# TIDA-010933-DCDC-Power.net
KiCad netlist of a schematic drawn in Altium Designer
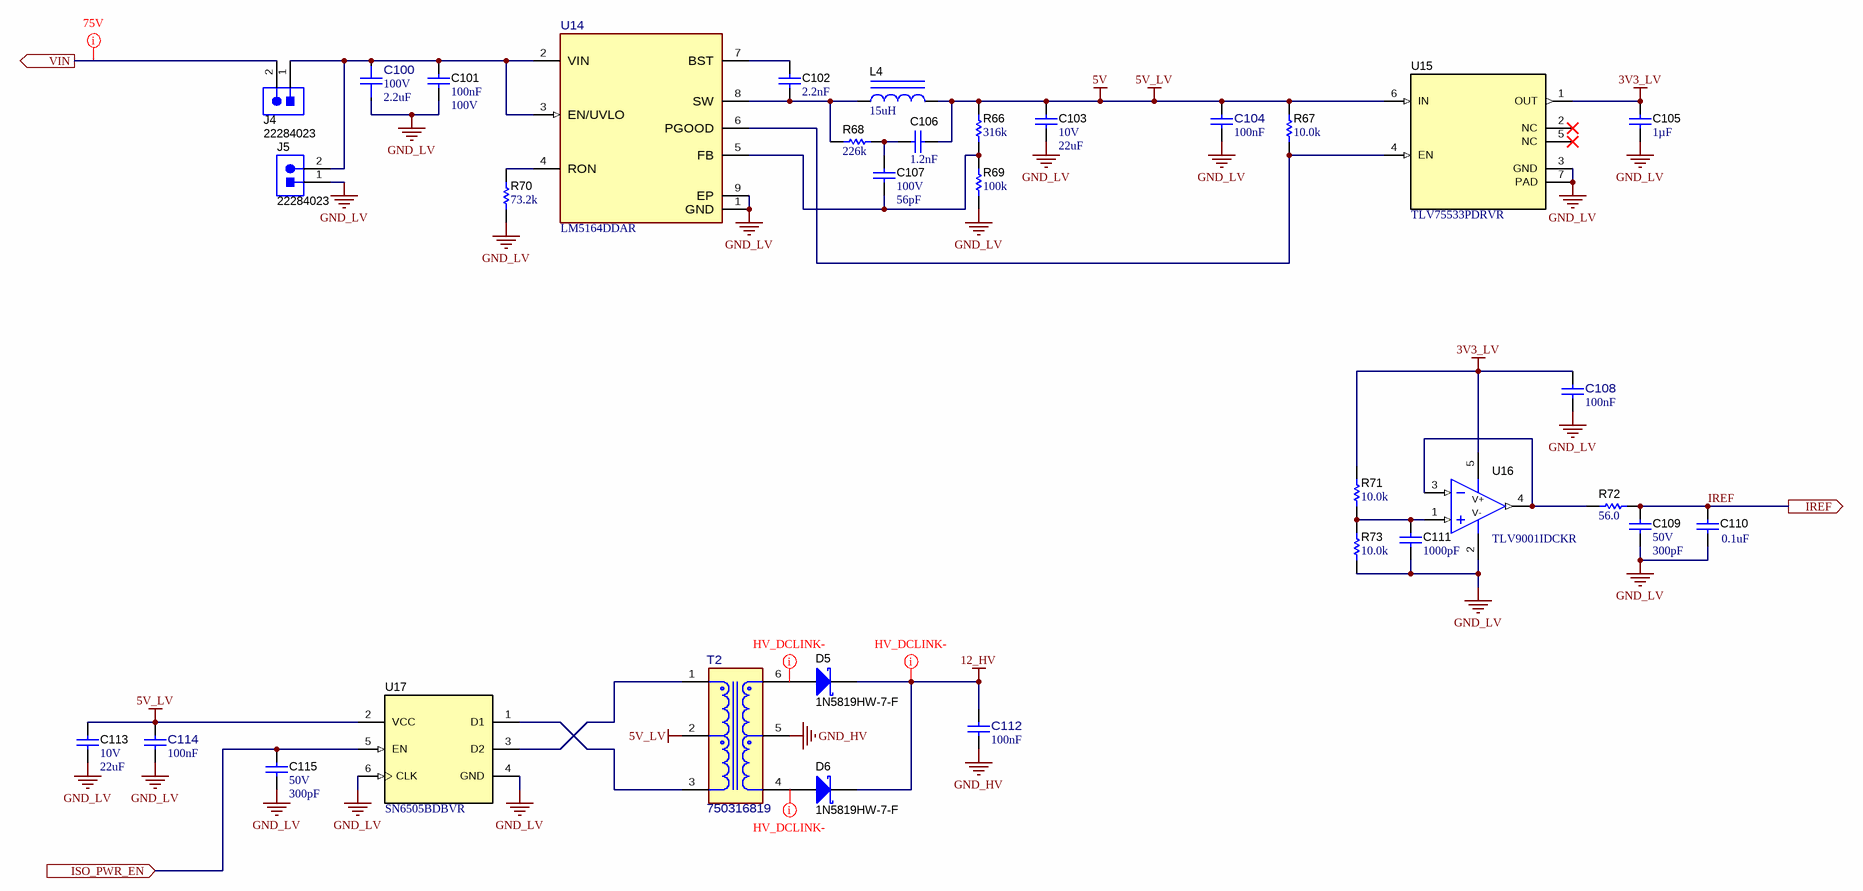
[diagram p0: TIDA-010933-DCDC-Power.SchDoc]

(export (version "E")
  (design (tool "Eeschema 10.0.6"))
  (components
    (comp (ref "C100")
      (value "C3225X7R2A225K230AB")
      (footprint "FP-C3225X7R2A225K230AB_1210-MFG")
      (description "CAP, CERM, 2.2 uF, 100 V, +/- 10%, X7R, 1210")
      (fields
        (field (name "VDC_V") "100V")
        (field (name "MANUFACTURER") "TDK")
        (field (name "VALUEDISPLAYED") "2.2uF")
      )
      (libsource (lib "Altium Vault - TI") (part "SYM-C3225X7R2A225K230AB"))
    )
    (comp (ref "C101")
      (value "GRM188R72A104KA35D")
      (footprint "0603")
      (description "CAP, CERM, 0.1 uF, 100 V, +/- 10%, X7R, 0603")
      (fields
        (field (name "MANUFACTURER") "MuRata")
        (field (name "CAP_F") "100nF")
        (field (name "VDC_V") "100V")
        (field (name "PUBLISHER") "Texas Instruments")
      )
      (libsource (lib "Altium Vault - TI") (part "Capacitor"))
    )
    (comp (ref "C102")
      (value "C0603C222K5RAC")
      (footprint "0603")
      (description "CAP, CERM, 2200 pF, 50 V, +/- 10%, X7R, 0603")
      (fields
        (field (name "MANUFACTURER") "Kemet")
        (field (name "CAP_F") "2.2nF")
        (field (name "PUBLISHER") "Texas Instruments")
      )
      (libsource (lib "Altium Vault - TI") (part "Capacitor"))
    )
    (comp (ref "C103")
      (value "GRM31CR71A226KE15L")
      (footprint "1206_180")
      (description "CAP, CERM, 22 uF, 10 V, +/- 10%, X7R, 1206")
      (fields
        (field (name "MANUFACTURER") "MuRata")
        (field (name "VDC_V") "10V")
        (field (name "VALUEDISPLAYED") "22uF")
        (field (name "PUBLISHER") "Texas Instruments")
      )
      (libsource (lib "Altium Vault - TI") (part "Capacitor"))
    )
    (comp (ref "C104")
      (value "CL10B104KB8NNNC")
      (footprint "FP-CL10B104KB8NNNC_0603-IPC_B")
      (description "CAP CER 0.1UF 50V X7R 0603")
      (fields (field (name "CAP_F") "100nF") (field (name "MANUFACTURER") "Samsung"))
      (libsource (lib "Altium Vault - TI") (part "SYM-CAPACITOR"))
    )
    (comp (ref "C105")
      (value "885012206026")
      (footprint "0603")
      (description "CAP, CERM, 1 uF, 10 V,+/- 10%, X7R, 0603")
      (fields
        (field (name "MANUFACTURER") "Wurth Elektronik")
        (field (name "CAP_F") "1µF")
        (field (name "PUBLISHER") "Texas Instruments")
      )
      (libsource (lib "Altium Vault - TI") (part "Capacitor"))
    )
    (comp (ref "C106")
      (value "GRM188R72A122KA01D")
      (footprint "0603")
      (description "CAP, CERM, 1200 pF, 100 V, +/- 10%, X7R, 0603")
      (fields
        (field (name "MANUFACTURER") "MuRata")
        (field (name "CAP_F") "1.2nF")
        (field (name "PUBLISHER") "Texas Instruments")
      )
      (libsource (lib "Altium Vault - TI") (part "Capacitor"))
    )
    (comp (ref "C107")
      (value "GRM1885C2A560JA01D")
      (footprint "0603")
      (description "CAP, CERM, 56 pF, 100 V, +/- 5%, C0G/NP0, 0603")
      (fields
        (field (name "MANUFACTURER") "MuRata")
        (field (name "VDC_V") "100V")
        (field (name "VALUEDISPLAYED") "56pF")
        (field (name "PUBLISHER") "Texas Instruments")
      )
      (libsource (lib "Altium Vault - TI") (part "Capacitor"))
    )
    (comp (ref "C108")
      (value "CL10B104KB8NNNC")
      (footprint "FP-CL10B104KB8NNNC_0603-IPC_B")
      (description "CAP CER 0.1UF 50V X7R 0603")
      (fields (field (name "CAP_F") "100nF") (field (name "MANUFACTURER") "Samsung"))
      (libsource (lib "Altium Vault - TI") (part "SYM-CAPACITOR"))
    )
    (comp (ref "C109")
      (value "GRM1885C1H301JA01D")
      (footprint "0603")
      (description "CAP, CERM, 300 pF, 50 V, +/- 5%, C0G/NP0, 0603")
      (fields
        (field (name "MANUFACTURER") "MuRata")
        (field (name "VDC_V") "50V")
        (field (name "VALUEDISPLAYED") "300pF")
        (field (name "PUBLISHER") "Texas Instruments")
      )
      (libsource (lib "Altium Vault - TI") (part "Capacitor"))
    )
    (comp (ref "C110")
      (value "GRM155R71E104KE14D")
      (footprint "0402")
      (description "CAP, CERM, 0.1 uF, 25 V, +/- 10%, X7R, 0402")
      (fields
        (field (name "MANUFACTURER") "MuRata")
        (field (name "VALUEDISPLAYED") "0.1uF")
        (field (name "PUBLISHER") "Texas Instruments")
      )
      (libsource (lib "Altium Vault - TI") (part "Capacitor"))
    )
    (comp (ref "C111")
      (value "CC0603JRNPO8BN102")
      (footprint "0603")
      (description "CAP, CERM, 1000 pF, 25 V,+/- 5%, C0G/NP0, 0603")
      (fields (field (name "VALUEDISPLAYED") "1000pF") (field (name "MANUFACTURER") "Yageo"))
      (libsource (lib "Altium Vault - TI") (part "Capacitor"))
    )
    (comp (ref "C112")
      (value "CL10B104KB8NNNC")
      (footprint "FP-CL10B104KB8NNNC_0603-IPC_B")
      (description "CAP CER 0.1UF 50V X7R 0603")
      (fields (field (name "CAP_F") "100nF") (field (name "MANUFACTURER") "Samsung"))
      (libsource (lib "Altium Vault - TI") (part "SYM-CAPACITOR"))
    )
    (comp (ref "C113")
      (value "GRM31CR71A226KE15L")
      (footprint "1206_180")
      (description "CAP, CERM, 22 uF, 10 V, +/- 10%, X7R, 1206")
      (fields
        (field (name "MANUFACTURER") "MuRata")
        (field (name "VDC_V") "10V")
        (field (name "VALUEDISPLAYED") "22uF")
        (field (name "PUBLISHER") "Texas Instruments")
      )
      (libsource (lib "Altium Vault - TI") (part "Capacitor"))
    )
    (comp (ref "C114")
      (value "CL10B104KB8NNNC")
      (footprint "FP-CL10B104KB8NNNC_0603-IPC_B")
      (description "CAP CER 0.1UF 50V X7R 0603")
      (fields (field (name "CAP_F") "100nF") (field (name "MANUFACTURER") "Samsung"))
      (libsource (lib "Altium Vault - TI") (part "SYM-CAPACITOR"))
    )
    (comp (ref "C115")
      (value "GRM1885C1H301JA01D")
      (footprint "0603")
      (description "CAP, CERM, 300 pF, 50 V, +/- 5%, C0G/NP0, 0603")
      (fields
        (field (name "MANUFACTURER") "MuRata")
        (field (name "VDC_V") "50V")
        (field (name "VALUEDISPLAYED") "300pF")
        (field (name "PUBLISHER") "Texas Instruments")
      )
      (libsource (lib "Altium Vault - TI") (part "Capacitor"))
    )
    (comp (ref "D5")
      (value "1N5819HW-7-F")
      (footprint "SOD-123")
      (description "Diode, Schottky, 40 V, 1 A, SOD-123")
      (fields (field (name "MANUFACTURER") "Diodes Inc."))
      (libsource (lib "Altium Vault - TI") (part "DIODE_SCHOTTKY"))
    )
    (comp (ref "D6")
      (value "1N5819HW-7-F")
      (footprint "SOD-123")
      (description "Diode, Schottky, 40 V, 1 A, SOD-123")
      (fields (field (name "MANUFACTURER") "Diodes Inc."))
      (libsource (lib "Altium Vault - TI") (part "DIODE_SCHOTTKY"))
    )
    (comp (ref "J4")
      (value "22284023")
      (footprint "Molex_0022284023")
      (description "Header, 2.54mm, 2x1, Tin, TH")
      (fields (field (name "MANUFACTURER") "Molex") (field (name "PUBLISHER") "Texas Instruments"))
      (libsource (lib "") (part "Header_2x1_1"))
    )
    (comp (ref "J5")
      (value "22284023")
      (footprint "Molex_0022284023")
      (description "Header, 2.54mm, 2x1, Tin, TH")
      (fields (field (name "MANUFACTURER") "Molex") (field (name "PUBLISHER") "Texas Instruments"))
      (libsource (lib "Altium Vault - TI") (part "Header_2x1"))
    )
    (comp (ref "L4")
      (value "SRP6540-150M")
      (footprint "SRP6540")
      (description "Inductor, Shielded, Ferrite, 15 uH, 2.9 A, 0.121 ohm, SMD")
      (fields
        (field (name "MANUFACTURER") "Bourns")
        (field (name "VALUEDISPLAYED") "15uH")
        (field (name "PUBLISHER") "Texas Instruments")
      )
      (libsource (lib "Altium Vault - TI") (part "Inductor_Iron"))
    )
    (comp (ref "R66")
      (value "RC0603FR-07316KL")
      (footprint "0603")
      (description "RES, 316 k, 1%, 0.1 W, 0603")
      (fields (field (name "MANUFACTURER") "Yageo") (field (name "VALUEDISPLAYED") "316k"))
      (libsource (lib "Altium Vault - TI") (part "Resistor"))
    )
    (comp (ref "R67")
      (value "RC0402FR-0710KL")
      (footprint "0402")
      (description "RES, 10.0 k, 1%, 0.063 W, 0402")
      (fields (field (name "MANUFACTURER") "Yageo America") (field (name "VALUEDISPLAYED") "10.0k"))
      (libsource (lib "Altium Vault - TI") (part "Resistor"))
    )
    (comp (ref "R68")
      (value "RC0603FR-07226KL")
      (footprint "0603")
      (description "RES, 226 k, 1%, 0.1 W, 0603")
      (fields (field (name "MANUFACTURER") "Yageo") (field (name "VALUEDISPLAYED") "226k"))
      (libsource (lib "Altium Vault - TI") (part "Resistor"))
    )
    (comp (ref "R69")
      (value "RC0603FR-07100KL")
      (footprint "0603")
      (description "RES, 100 k, 1%, 0.1 W, 0603")
      (fields (field (name "MANUFACTURER") "Yageo") (field (name "VALUEDISPLAYED") "100k"))
      (libsource (lib "Altium Vault - TI") (part "Resistor"))
    )
    (comp (ref "R70")
      (value "RC0603FR-0773K2L")
      (footprint "0603")
      (description "RES, 73.2 k, 1%, 0.1 W, 0603")
      (fields (field (name "MANUFACTURER") "Yageo") (field (name "VALUEDISPLAYED") "73.2k"))
      (libsource (lib "Altium Vault - TI") (part "Resistor"))
    )
    (comp (ref "R71")
      (value "RT0603BRD0710KL")
      (footprint "0603")
      (description "RES, 10.0 k, 0.1%, 0.1 W, 0603")
      (fields
        (field (name "MANUFACTURER") "Yageo America")
        (field (name "VALUEDISPLAYED") "10.0k")
        (field (name "PUBLISHER") "Texas Instruments")
      )
      (libsource (lib "Altium Vault - TI") (part "Resistor"))
    )
    (comp (ref "R72")
      (value "RC0603FR-0756RL")
      (footprint "0603")
      (description "RES, 56.0, 1%, 0.1 W, 0603")
      (fields (field (name "MANUFACTURER") "Yageo") (field (name "VALUEDISPLAYED") "56.0"))
      (libsource (lib "Altium Vault - TI") (part "Resistor"))
    )
    (comp (ref "R73")
      (value "RT0603BRD0710KL")
      (footprint "0603")
      (description "RES, 10.0 k, 0.1%, 0.1 W, 0603")
      (fields
        (field (name "MANUFACTURER") "Yageo America")
        (field (name "VALUEDISPLAYED") "10.0k")
        (field (name "PUBLISHER") "Texas Instruments")
      )
      (libsource (lib "Altium Vault - TI") (part "Resistor"))
    )
    (comp (ref "T2")
      (value "750316819")
      (footprint "FP-750316819_SMT_XFRMR_9MM25_8MM30-MFG")
      (fields
        (field (name "MOUSER PART NUMBER") "710-750316819")
        (field (name "DIGIKEY PART NUMBER") "732-750316819CT-ND")
        (field (name "MANUFACTURER") "Wurth Electronics")
      )
      (libsource (lib "Altium Vault - TI") (part "SYM-750316819"))
    )
    (comp (ref "U14")
      (value "LM5164DDAR")
      (footprint "DDA0008E-MFG")
      (fields
        (field (name "PARTNUMBER") "LM5164DDAR")
        (field (name "MOUSER PART NUMBER") "595-LM5164DDAR")
        (field (name "MANUFACTURER") "Texas Instruments")
        (field (name "DIGIKEY PART NUMBER") "296-LM5164DDARCT-ND")
      )
      (libsource (lib "Altium Vault - TI") (part "SYM-LM5164DDAR"))
    )
    (comp (ref "U15")
      (value "TLV75533PDRVR")
      (footprint "DRV0006A")
      (description "500mA LDO, DRV0006A (WSON-6)")
      (fields
        (field (name "PARTNUMBER") "TLV75533PDRVR")
        (field (name "MANUFACTURER") "Texas Instruments")
        (field (name "PUBLISHER") "Texas Instruments")
      )
      (libsource (lib "Altium Vault - TI") (part "TLV75533PDRV"))
    )
    (comp (ref "U16")
      (value "TLV9001IDCKR")
      (footprint "DCK0005A_N")
      (description "Low-Power, Rail-to-Rail In and Out, 1-MHz Operational Amplifier, DCK0005A (SOT-SC70-5)")
      (fields
        (field (name "ALTERNATE PARTNUMBER") "TLV9001IDCKT")
        (field (name "MANUFACTURER") "Texas Instruments")
        (field (name "PARTNUMBER") "TLV9001IDCKR")
      )
      (libsource (lib "Altium Vault - TI") (part "OPAMP_SINGLE_SOT321"))
    )
    (comp (ref "U17")
      (value "SN6505BDBVR")
      (footprint "DBV0006A_L")
      (description "Low-Noise 1 A, 420 kHz Transformer Driver, DBV0006A (SOT-23-6)")
      (fields
        (field (name "PARTNUMBER") "SN6505BDBVR")
        (field (name "MANUFACTURER") "Texas Instruments")
        (field (name "ALTERNATE PARTNUMBER") "SN6505BDBVT")
        (field (name "PUBLISHER") "Texas Instruments")
      )
      (libsource (lib "Altium Vault - TI") (part "SN6505"))
    )
  )
  (nets
    (net (code "1") (name "/IREF") (class "Default")
      (node (ref "C109") (pin "1") (pinfunction "1_1") (pintype "passive"))
      (node (ref "C110") (pin "1") (pinfunction "1_1") (pintype "passive"))
      (node (ref "R72") (pin "2") (pinfunction "2_2") (pintype "passive"))
    )
    (net (code "2") (name "/ISO_PWR_EN") (class "Default")
      (node (ref "C115") (pin "1") (pinfunction "1_1") (pintype "passive"))
      (node (ref "U17") (pin "5") (pinfunction "EN_5") (pintype "input"))
    )
    (net (code "3") (name "/VIN") (class "Default")
      (node (ref "J4") (pin "2") (pinfunction "2_2") (pintype "passive"))
    )
    (net (code "4") (name "3V3_LV") (class "Default")
      (node (ref "C105") (pin "1") (pinfunction "1_1") (pintype "passive"))
      (node (ref "C108") (pin "1") (pinfunction "1_1") (pintype "passive"))
      (node (ref "R71") (pin "1") (pinfunction "1_1") (pintype "passive"))
      (node (ref "U15") (pin "1") (pinfunction "OUT_1") (pintype "output"))
      (node (ref "U16") (pin "5") (pinfunction "V+_5") (pintype "power_in"))
    )
    (net (code "5") (name "5V") (class "Default")
      (node (ref "C103") (pin "1") (pinfunction "1_1") (pintype "passive"))
      (node (ref "C104") (pin "2") (pinfunction "2_2") (pintype "passive"))
      (node (ref "C106") (pin "1") (pinfunction "1_1") (pintype "passive"))
      (node (ref "C113") (pin "1") (pinfunction "1_1") (pintype "passive"))
      (node (ref "C114") (pin "1") (pinfunction "1_1") (pintype "passive"))
      (node (ref "L4") (pin "2") (pinfunction "2_2") (pintype "passive"))
      (node (ref "R66") (pin "2") (pinfunction "2_2") (pintype "passive"))
      (node (ref "R67") (pin "2") (pinfunction "2_2") (pintype "passive"))
      (node (ref "T2") (pin "2") (pinfunction "2_2") (pintype "passive"))
      (node (ref "U15") (pin "6") (pinfunction "IN_6") (pintype "input"))
      (node (ref "U17") (pin "2") (pinfunction "VCC_2") (pintype "power_in"))
    )
    (net (code "6") (name "12_HV") (class "Default")
      (node (ref "C112") (pin "1") (pinfunction "1_1") (pintype "passive"))
      (node (ref "D5") (pin "1") (pinfunction "K_1") (pintype "passive"))
      (node (ref "D6") (pin "1") (pinfunction "K_1") (pintype "passive"))
    )
    (net (code "7") (name "GND_HV") (class "Default")
      (node (ref "C112") (pin "2") (pinfunction "2_2") (pintype "passive"))
      (node (ref "T2") (pin "5") (pinfunction "5_5") (pintype "passive"))
    )
    (net (code "8") (name "GND_LV") (class "Default")
      (node (ref "C100") (pin "1") (pinfunction "1_1") (pintype "passive"))
      (node (ref "C101") (pin "2") (pinfunction "2_2") (pintype "passive"))
      (node (ref "C103") (pin "2") (pinfunction "2_2") (pintype "passive"))
      (node (ref "C104") (pin "1") (pinfunction "1_1") (pintype "passive"))
      (node (ref "C105") (pin "2") (pinfunction "2_2") (pintype "passive"))
      (node (ref "C108") (pin "2") (pinfunction "2_2") (pintype "passive"))
      (node (ref "C109") (pin "2") (pinfunction "2_2") (pintype "passive"))
      (node (ref "C110") (pin "2") (pinfunction "2_2") (pintype "passive"))
      (node (ref "C111") (pin "2") (pinfunction "2_2") (pintype "passive"))
      (node (ref "C113") (pin "2") (pinfunction "2_2") (pintype "passive"))
      (node (ref "C114") (pin "2") (pinfunction "2_2") (pintype "passive"))
      (node (ref "C115") (pin "2") (pinfunction "2_2") (pintype "passive"))
      (node (ref "J5") (pin "1") (pinfunction "1_1") (pintype "passive"))
      (node (ref "R69") (pin "1") (pinfunction "1_1") (pintype "passive"))
      (node (ref "R70") (pin "1") (pinfunction "1_1") (pintype "passive"))
      (node (ref "R73") (pin "2") (pinfunction "2_2") (pintype "passive"))
      (node (ref "U14") (pin "1") (pinfunction "GND_1") (pintype "power_in"))
      (node (ref "U14") (pin "9") (pinfunction "EP_9") (pintype "passive"))
      (node (ref "U15") (pin "3") (pinfunction "GND_3") (pintype "power_in"))
      (node (ref "U15") (pin "7") (pinfunction "PAD_7") (pintype "power_in"))
      (node (ref "U16") (pin "2") (pinfunction "V-_2") (pintype "power_in"))
      (node (ref "U17") (pin "4") (pinfunction "GND_4") (pintype "power_in"))
      (node (ref "U17") (pin "6") (pinfunction "CLK_6") (pintype "input"))
    )
    (net (code "9") (name "Net-(C106-Pad2)") (class "Default")
      (node (ref "C106") (pin "2") (pinfunction "2_2") (pintype "passive"))
      (node (ref "C107") (pin "1") (pinfunction "1_1") (pintype "passive"))
      (node (ref "R68") (pin "2") (pinfunction "2_2") (pintype "passive"))
    )
    (net (code "10") (name "Net-(D5-A)") (class "Default")
      (node (ref "D5") (pin "2") (pinfunction "A_2") (pintype "passive"))
      (node (ref "T2") (pin "6") (pinfunction "6_6") (pintype "passive"))
    )
    (net (code "11") (name "Net-(D6-A)") (class "Default")
      (node (ref "D6") (pin "2") (pinfunction "A_2") (pintype "passive"))
      (node (ref "T2") (pin "4") (pinfunction "4_4") (pintype "passive"))
    )
    (net (code "12") (name "Net-(U14-BST)") (class "Default")
      (node (ref "C102") (pin "1") (pinfunction "1_1") (pintype "passive"))
      (node (ref "U14") (pin "7") (pinfunction "BST_7") (pintype "passive"))
    )
    (net (code "13") (name "Net-(U14-EN{slash}UVLO)") (class "Default")
      (node (ref "C100") (pin "2") (pinfunction "2_2") (pintype "passive"))
      (node (ref "C101") (pin "1") (pinfunction "1_1") (pintype "passive"))
      (node (ref "J4") (pin "1") (pinfunction "1_1") (pintype "passive"))
      (node (ref "J5") (pin "2") (pinfunction "2_2") (pintype "passive"))
      (node (ref "U14") (pin "2") (pinfunction "VIN_2") (pintype "power_in"))
      (node (ref "U14") (pin "3") (pinfunction "EN/UVLO_3") (pintype "input"))
    )
    (net (code "14") (name "Net-(U14-FB)") (class "Default")
      (node (ref "C107") (pin "2") (pinfunction "2_2") (pintype "passive"))
      (node (ref "R66") (pin "1") (pinfunction "1_1") (pintype "passive"))
      (node (ref "R69") (pin "2") (pinfunction "2_2") (pintype "passive"))
      (node (ref "U14") (pin "5") (pinfunction "FB_5") (pintype "passive"))
    )
    (net (code "15") (name "Net-(U14-PGOOD)") (class "Default")
      (node (ref "R67") (pin "1") (pinfunction "1_1") (pintype "passive"))
      (node (ref "U14") (pin "6") (pinfunction "PGOOD_6") (pintype "open_collector"))
      (node (ref "U15") (pin "4") (pinfunction "EN_4") (pintype "input"))
    )
    (net (code "16") (name "Net-(U14-RON)") (class "Default")
      (node (ref "R70") (pin "2") (pinfunction "2_2") (pintype "passive"))
      (node (ref "U14") (pin "4") (pinfunction "RON_4") (pintype "passive"))
    )
    (net (code "17") (name "Net-(U14-SW)") (class "Default")
      (node (ref "C102") (pin "2") (pinfunction "2_2") (pintype "passive"))
      (node (ref "L4") (pin "1") (pinfunction "1_1") (pintype "passive"))
      (node (ref "R68") (pin "1") (pinfunction "1_1") (pintype "passive"))
      (node (ref "U14") (pin "8") (pinfunction "SW_8") (pintype "passive"))
    )
    (net (code "18") (name "Net-(U16-IN+)") (class "Default")
      (node (ref "C111") (pin "1") (pinfunction "1_1") (pintype "passive"))
      (node (ref "R71") (pin "2") (pinfunction "2_2") (pintype "passive"))
      (node (ref "R73") (pin "1") (pinfunction "1_1") (pintype "passive"))
      (node (ref "U16") (pin "1") (pinfunction "IN+_1") (pintype "input"))
    )
    (net (code "19") (name "Net-(U16-IN-)") (class "Default")
      (node (ref "R72") (pin "1") (pinfunction "1_1") (pintype "passive"))
      (node (ref "U16") (pin "3") (pinfunction "IN-_3") (pintype "input"))
      (node (ref "U16") (pin "4") (pinfunction "OUT_4") (pintype "output"))
    )
    (net (code "20") (name "Net-(U17-D1)") (class "Default")
      (node (ref "T2") (pin "3") (pinfunction "3_3") (pintype "passive"))
      (node (ref "U17") (pin "1") (pinfunction "D1_1") (pintype "open_collector"))
    )
    (net (code "21") (name "Net-(U17-D2)") (class "Default")
      (node (ref "T2") (pin "1") (pinfunction "1_1") (pintype "passive"))
      (node (ref "U17") (pin "3") (pinfunction "D2_3") (pintype "open_collector"))
    )
    (net (code "22") (name "unconnected-(U15-NC-Pad2)") (class "Default")
      (node (ref "U15") (pin "2") (pinfunction "NC_2") (pintype "passive+no_connect"))
    )
    (net (code "23") (name "unconnected-(U15-NC-Pad5)") (class "Default")
      (node (ref "U15") (pin "5") (pinfunction "NC_5") (pintype "passive+no_connect"))
    )
  )
)
